# differential_receiver.net
KiCad netlist of a schematic drawn in Altium Designer
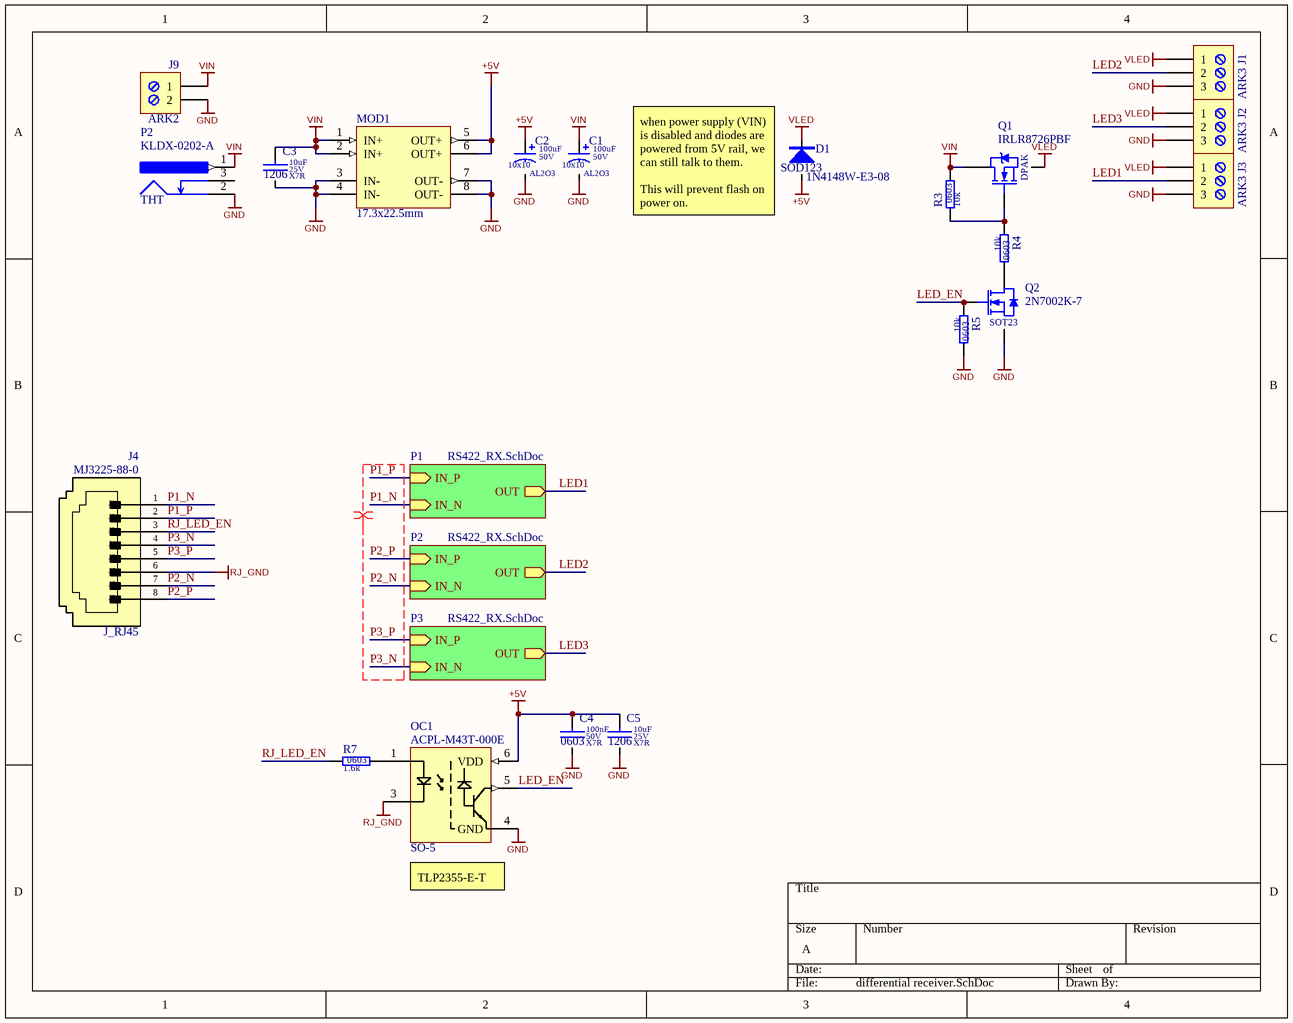
[diagram p0: differential receiver.SchDoc]

(export (version "E")
  (design (tool "Eeschema 10.0.6"))
  (components
    (comp (ref "C1")
      (value "100uF")
      (footprint "CE_D_10x10_SMD")
      (description "Polarized Capacitor")
      (fields
        (field (name "DIELECTRIC") "AL2O3")
        (field (name "SCH_FOOTPRINT") "10x10")
        (field (name "VOLTAGE") "50V")
        (field (name "PART NUMBER") "CE_100uF_50V_AL2O3_10x10_20")
        (field (name "MANUFACTURER") "Nichicon")
      )
      (libsource (lib "Library") (part "CE"))
    )
    (comp (ref "C2")
      (value "100uF")
      (footprint "CE_D_10x10_SMD")
      (description "Polarized Capacitor")
      (fields
        (field (name "DIELECTRIC") "AL2O3")
        (field (name "SCH_FOOTPRINT") "10x10")
        (field (name "VOLTAGE") "50V")
        (field (name "PART NUMBER") "CE_100uF_50V_AL2O3_10x10_20")
        (field (name "MANUFACTURER") "Nichicon")
      )
      (libsource (lib "Library") (part "CE"))
    )
    (comp (ref "C3")
      (value "10uF")
      (footprint "C_1206_3216")
      (description "Capacitor")
      (fields
        (field (name "DIELECTRIC") "X7R")
        (field (name "VOLTAGE") "25V")
        (field (name "SCH_FOOTPRINT") "1206")
        (field (name "PART NUMBER") "C_10uF_25V_X7R_1206_10")
        (field (name "MANUFACTURER") "Samsung")
      )
      (libsource (lib "Library") (part "C"))
    )
    (comp (ref "C4")
      (value "100nF")
      (footprint "C_0603_1608")
      (description "Capacitor")
      (fields
        (field (name "DIELECTRIC") "X7R")
        (field (name "VOLTAGE") "50V")
        (field (name "SCH_FOOTPRINT") "0603")
        (field (name "PART NUMBER") "C_100nF_50V_X7R_0603_5")
        (field (name "MANUFACTURER") "Samsung")
      )
      (libsource (lib "Library") (part "C"))
    )
    (comp (ref "C5")
      (value "10uF")
      (footprint "C_1206_3216")
      (description "Capacitor")
      (fields
        (field (name "DIELECTRIC") "X7R")
        (field (name "VOLTAGE") "25V")
        (field (name "SCH_FOOTPRINT") "1206")
        (field (name "PART NUMBER") "C_10uF_25V_X7R_1206_10")
        (field (name "MANUFACTURER") "Samsung")
      )
      (libsource (lib "Library") (part "C"))
    )
    (comp (ref "D1")
      (value "1N4148W-E3-08")
      (footprint "SOD123")
      (fields
        (field (name "SCH_FOOTPRINT") "SOD123")
        (field (name "PART NUMBER") "D_1N4148W_0A15_75V_SOD123")
        (field (name "VOLTAGE") "75")
        (field (name "MANUFACTURER") "Vishay")
      )
      (libsource (lib "Library") (part "D"))
    )
    (comp (ref "J1")
      (value "ARK3")
      (footprint "J_ARK3")
      (description "ARK Screw terminal, 3-Pin")
      (fields
        (field (name "SCH_FOOTPRINT") "ARK3")
        (field (name "PART NUMBER") "J_TB-5.0-P-3P")
        (field (name "MANUFACTURER") "DEGSON ELECTRONICS")
      )
      (libsource (lib "Library") (part "J_ARK3"))
    )
    (comp (ref "J2")
      (value "ARK3")
      (footprint "J_ARK3")
      (description "ARK Screw terminal, 3-Pin")
      (fields
        (field (name "SCH_FOOTPRINT") "ARK3")
        (field (name "PART NUMBER") "J_TB-5.0-P-3P")
        (field (name "MANUFACTURER") "DEGSON ELECTRONICS")
      )
      (libsource (lib "Library") (part "J_ARK3"))
    )
    (comp (ref "J3")
      (value "ARK3")
      (footprint "J_ARK3")
      (description "ARK Screw terminal, 3-Pin")
      (fields
        (field (name "SCH_FOOTPRINT") "ARK3")
        (field (name "PART NUMBER") "J_TB-5.0-P-3P")
        (field (name "MANUFACTURER") "DEGSON ELECTRONICS")
      )
      (libsource (lib "Library") (part "J_ARK3"))
    )
    (comp (ref "J4")
      (value "MJ3225-88-0")
      (footprint "J_RJ45_MJ3225-88-0")
      (fields
        (field (name "SCH_FOOTPRINT") "J_RJ45")
        (field (name "PART NUMBER") "J_RJ45_MJ3225-88-0")
        (field (name "MANUFACTURER") "Global Connector Technology")
        (field (name "Comment") "Modular Connector, Modular Jack, 1 x 1 (Port), 8P8C, Cat3")
      )
      (libsource (lib "Library") (part "J_RJ45"))
    )
    (comp (ref "J9")
      (value "ARK2")
      (footprint "J_ARK2")
      (description "ARK Screw terminal, 2-Pin")
      (fields
        (field (name "SCH_FOOTPRINT") "ARK2")
        (field (name "PART NUMBER") "J_TB-5.0-P-2P")
        (field (name "MANUFACTURER") "DEGSON ELECTRONICS")
      )
      (libsource (lib "Library") (part "J_ARK2"))
    )
    (comp (ref "MOD1")
      (value "Low cost, Aliexpress-ready DC-DC buck converter using MP1584")
      (footprint "MOD_BUCK_MP1584")
      (fields (field (name "SCH_FOOTPRINT") "17.3x22.5mm") (field (name "PART NUMBER") "MOD_BUCK_MP1584"))
      (libsource (lib "Library") (part "MOD_BUCK_MP1584"))
    )
    (comp (ref "OC1")
      (value "ACPL-M43T-000E")
      (footprint "SO-5")
      (fields
        (field (name "SCH_FOOTPRINT") "SO-5")
        (field (name "PART NUMBER") "OC_ACPL-M43T-000E")
        (field (name "MANUFACTURER") "Broadcom")
        (field (name "Comment") "Optocoupler DC-IN 1-CH Transistor With Base DC-OUT Automotive")
      )
      (libsource (lib "Library") (part "OC_ACPL-M43T"))
    )
    (comp (ref "P2")
      (value "KLDX-0202-A")
      (footprint "P_KLDX-0202-A")
      (description "Typical 3-pin jack power connector with switch")
      (fields
        (field (name "SCH_FOOTPRINT") "THT")
        (field (name "PART NUMBER") "P_KLDX-0202-A")
        (field (name "MANUFACTURER") "Kycon")
      )
      (libsource (lib "Library") (part "P_DC_JACK"))
    )
    (comp (ref "Q1")
      (value "IRLR8726PBF")
      (footprint "DPAK_TO252-3_SC63_M")
      (fields
        (field (name "SCH_FOOTPRINT") "DPAK")
        (field (name "PART NUMBER") "QNS_IRLR8726PBF")
        (field (name "VOLTAGE") "30V")
        (field (name "MANUFACTURER") "Infineon")
      )
      (libsource (lib "Library") (part "QNS_GDS"))
    )
    (comp (ref "Q2")
      (value "2N7002K-7")
      (footprint "SOT23_TO236_SC59")
      (fields
        (field (name "SCH_FOOTPRINT") "SOT23")
        (field (name "PART NUMBER") "QN_2N7002K-7")
        (field (name "VOLTAGE") "60V")
        (field (name "MANUFACTURER") "Diodes Inc")
      )
      (libsource (lib "Library") (part "QN_GSD"))
    )
    (comp (ref "R3")
      (value "10k")
      (footprint "R_0603_1608")
      (fields
        (field (name "SCH_FOOTPRINT") "0603")
        (field (name "PART NUMBER") "R_10k_0603_1")
        (field (name "VOLTAGE") "75V")
        (field (name "POWER") "100mW")
      )
      (libsource (lib "Library") (part "R"))
    )
    (comp (ref "R4")
      (value "10k")
      (footprint "R_0603_1608")
      (fields
        (field (name "SCH_FOOTPRINT") "0603")
        (field (name "PART NUMBER") "R_10k_0603_1")
        (field (name "VOLTAGE") "75V")
        (field (name "POWER") "100mW")
      )
      (libsource (lib "Library") (part "R"))
    )
    (comp (ref "R5")
      (value "10k")
      (footprint "R_0603_1608")
      (fields
        (field (name "SCH_FOOTPRINT") "0603")
        (field (name "PART NUMBER") "R_10k_0603_1")
        (field (name "VOLTAGE") "75V")
        (field (name "POWER") "100mW")
      )
      (libsource (lib "Library") (part "R"))
    )
    (comp (ref "R7")
      (value "1.6k")
      (footprint "R_0603_1608")
      (fields
        (field (name "SCH_FOOTPRINT") "0603")
        (field (name "PART NUMBER") "R_1.6k_0603_1_AECQ0")
        (field (name "VOLTAGE") "75V")
        (field (name "POWER") "100mW")
      )
      (libsource (lib "Library") (part "R"))
    )
  )
  (nets
    (net (code "1") (name "+5V") (class "Default")
      (node (ref "C2") (pin "1") (pinfunction "1_1") (pintype "passive"))
      (node (ref "C4") (pin "1") (pinfunction "1_1") (pintype "passive"))
      (node (ref "C5") (pin "1") (pinfunction "1_1") (pintype "passive"))
      (node (ref "D1") (pin "2") (pintype "passive"))
      (node (ref "MOD1") (pin "5") (pinfunction "OUT+_5") (pintype "output"))
      (node (ref "MOD1") (pin "6") (pinfunction "OUT+_6") (pintype "passive"))
      (node (ref "OC1") (pin "6") (pinfunction "VDD_6") (pintype "input"))
    )
    (net (code "2") (name "/LED1") (class "Default")
      (node (ref "J3") (pin "2") (pinfunction "2_2") (pintype "passive"))
    )
    (net (code "3") (name "/LED2") (class "Default")
      (node (ref "J1") (pin "2") (pinfunction "2_2") (pintype "passive"))
    )
    (net (code "4") (name "/LED3") (class "Default")
      (node (ref "J2") (pin "2") (pinfunction "2_2") (pintype "passive"))
    )
    (net (code "5") (name "/LED_EN") (class "Default")
      (node (ref "OC1") (pin "5") (pinfunction "5_5") (pintype "output"))
      (node (ref "Q2") (pin "1") (pinfunction "G_1") (pintype "passive"))
      (node (ref "R5") (pin "1") (pinfunction "1_1") (pintype "passive"))
    )
    (net (code "6") (name "/P1_N") (class "Default") (node (ref "J4") (pin "1") (pintype "passive")))
    (net (code "7") (name "/P1_P") (class "Default") (node (ref "J4") (pin "2") (pintype "passive")))
    (net (code "8") (name "/P2_N") (class "Default") (node (ref "J4") (pin "7") (pintype "passive")))
    (net (code "9") (name "/P2_P") (class "Default") (node (ref "J4") (pin "8") (pintype "passive")))
    (net (code "10") (name "/P3_N") (class "Default") (node (ref "J4") (pin "4") (pintype "passive")))
    (net (code "11") (name "/P3_P") (class "Default") (node (ref "J4") (pin "5") (pintype "passive")))
    (net (code "12") (name "/RJ_LED_EN") (class "Default")
      (node (ref "J4") (pin "3") (pintype "passive"))
      (node (ref "R7") (pin "1") (pinfunction "1_1") (pintype "passive"))
    )
    (net (code "13") (name "GND") (class "Default")
      (node (ref "C1") (pin "2") (pinfunction "2_2") (pintype "passive"))
      (node (ref "C2") (pin "2") (pinfunction "2_2") (pintype "passive"))
      (node (ref "C3") (pin "2") (pinfunction "2_2") (pintype "passive"))
      (node (ref "C4") (pin "2") (pinfunction "2_2") (pintype "passive"))
      (node (ref "C5") (pin "2") (pinfunction "2_2") (pintype "passive"))
      (node (ref "J1") (pin "3") (pinfunction "3_3") (pintype "passive"))
      (node (ref "J2") (pin "3") (pinfunction "3_3") (pintype "passive"))
      (node (ref "J3") (pin "3") (pinfunction "3_3") (pintype "passive"))
      (node (ref "J9") (pin "2") (pinfunction "2_2") (pintype "passive"))
      (node (ref "MOD1") (pin "3") (pinfunction "IN-_3") (pintype "power_in"))
      (node (ref "MOD1") (pin "4") (pinfunction "IN-_4") (pintype "power_in"))
      (node (ref "MOD1") (pin "7") (pinfunction "OUT-_7") (pintype "output"))
      (node (ref "MOD1") (pin "8") (pinfunction "OUT-_8") (pintype "passive"))
      (node (ref "OC1") (pin "4") (pinfunction "GND_4") (pintype "power_in"))
      (node (ref "P2") (pin "2") (pinfunction "2_2") (pintype "passive"))
      (node (ref "Q2") (pin "2") (pinfunction "S_2") (pintype "passive"))
      (node (ref "R5") (pin "2") (pinfunction "2_2") (pintype "passive"))
    )
    (net (code "14") (name "Net-(OC1-Pad1)") (class "Default")
      (node (ref "OC1") (pin "1") (pinfunction "1_1") (pintype "passive"))
      (node (ref "R7") (pin "2") (pinfunction "2_2") (pintype "passive"))
    )
    (net (code "15") (name "Net-(Q1-G)") (class "Default")
      (node (ref "Q1") (pin "1") (pinfunction "G_1") (pintype "passive"))
      (node (ref "R3") (pin "1") (pinfunction "1_1") (pintype "passive"))
      (node (ref "R4") (pin "1") (pinfunction "1_1") (pintype "passive"))
    )
    (net (code "16") (name "Net-(Q2-D)") (class "Default")
      (node (ref "Q2") (pin "3") (pinfunction "D_3") (pintype "passive"))
      (node (ref "R4") (pin "2") (pinfunction "2_2") (pintype "passive"))
    )
    (net (code "17") (name "RJ_GND") (class "Default")
      (node (ref "J4") (pin "6") (pintype "passive"))
      (node (ref "OC1") (pin "3") (pinfunction "3_3") (pintype "passive"))
    )
    (net (code "18") (name "VIN") (class "Default")
      (node (ref "C1") (pin "1") (pinfunction "1_1") (pintype "passive"))
      (node (ref "C3") (pin "1") (pinfunction "1_1") (pintype "passive"))
      (node (ref "J9") (pin "1") (pinfunction "1_1") (pintype "passive"))
      (node (ref "MOD1") (pin "1") (pinfunction "IN+_1") (pintype "input"))
      (node (ref "MOD1") (pin "2") (pinfunction "IN+_2") (pintype "input"))
      (node (ref "P2") (pin "1") (pinfunction "1_1") (pintype "output"))
      (node (ref "Q1") (pin "2") (pinfunction "D_2") (pintype "passive"))
      (node (ref "R3") (pin "2") (pinfunction "2_2") (pintype "passive"))
    )
    (net (code "19") (name "VLED") (class "Default")
      (node (ref "D1") (pin "1") (pintype "passive"))
      (node (ref "J1") (pin "1") (pinfunction "1_1") (pintype "passive"))
      (node (ref "J2") (pin "1") (pinfunction "1_1") (pintype "passive"))
      (node (ref "J3") (pin "1") (pinfunction "1_1") (pintype "passive"))
      (node (ref "Q1") (pin "3") (pinfunction "S_3") (pintype "passive"))
    )
    (net (code "20") (name "unconnected-(P2-Pad3)") (class "Default")
      (node (ref "P2") (pin "3") (pinfunction "3_3") (pintype "passive"))
    )
  )
)
